# dnc.net
KiCad netlist of a schematic drawn in EAGLE
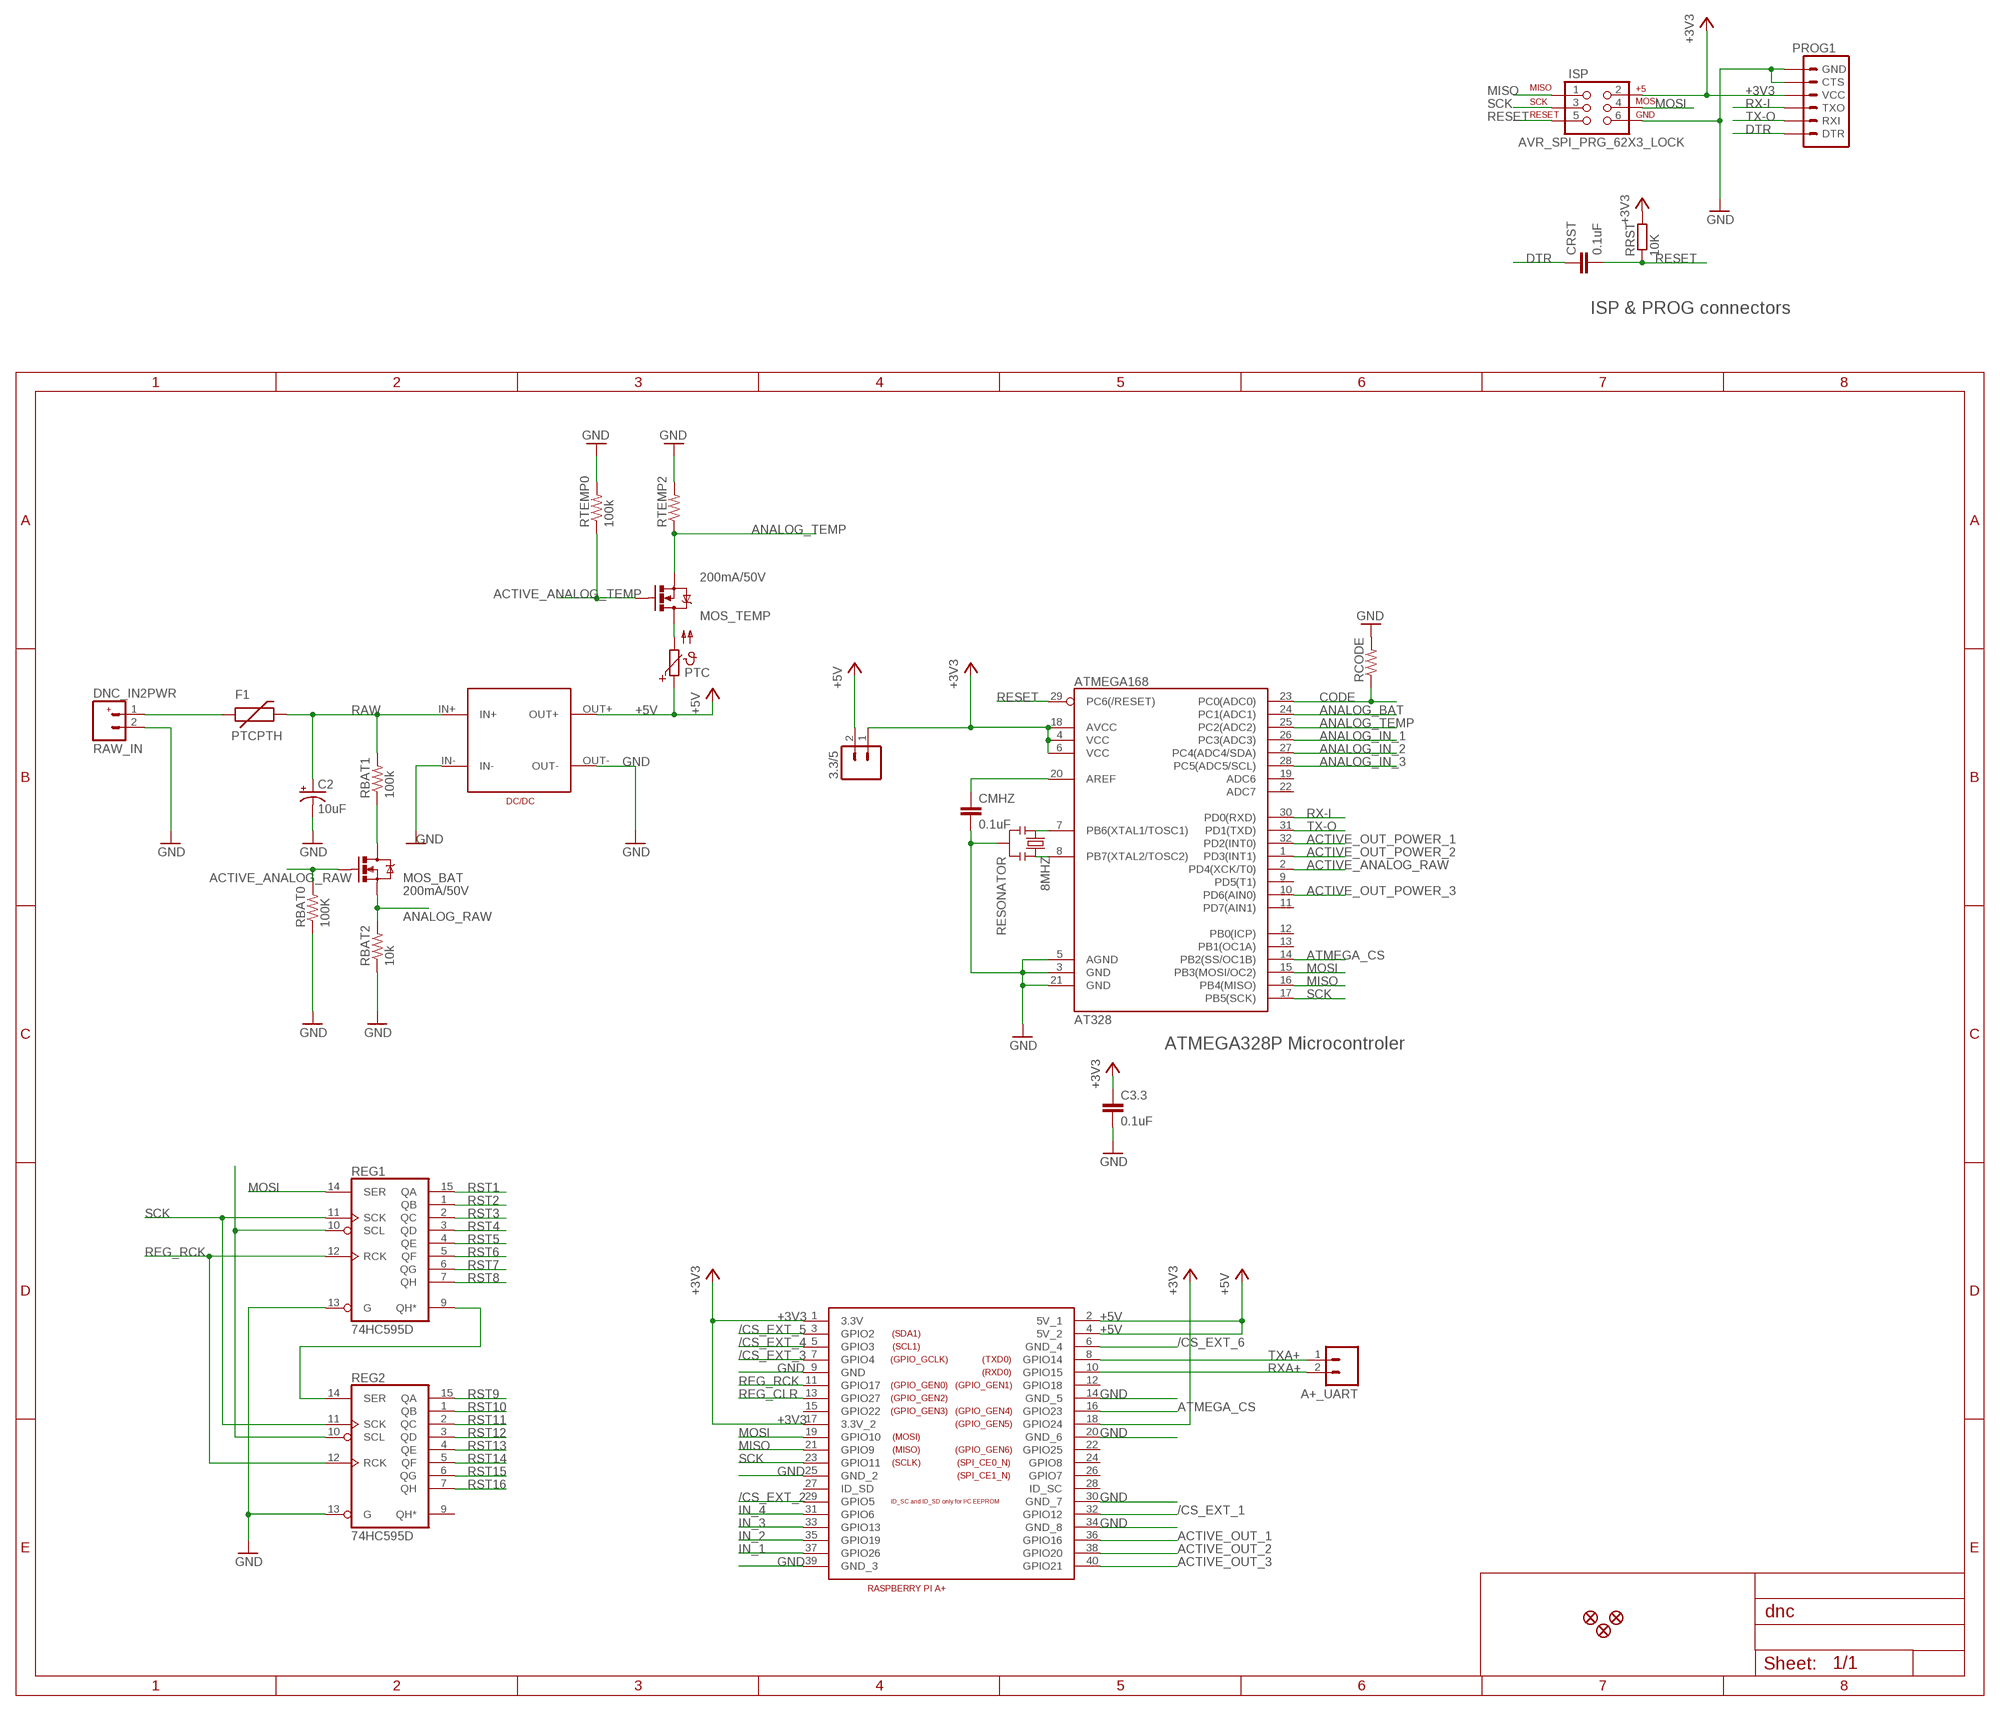
[diagram p0: schematic, sheet 1, part 1 of 2]
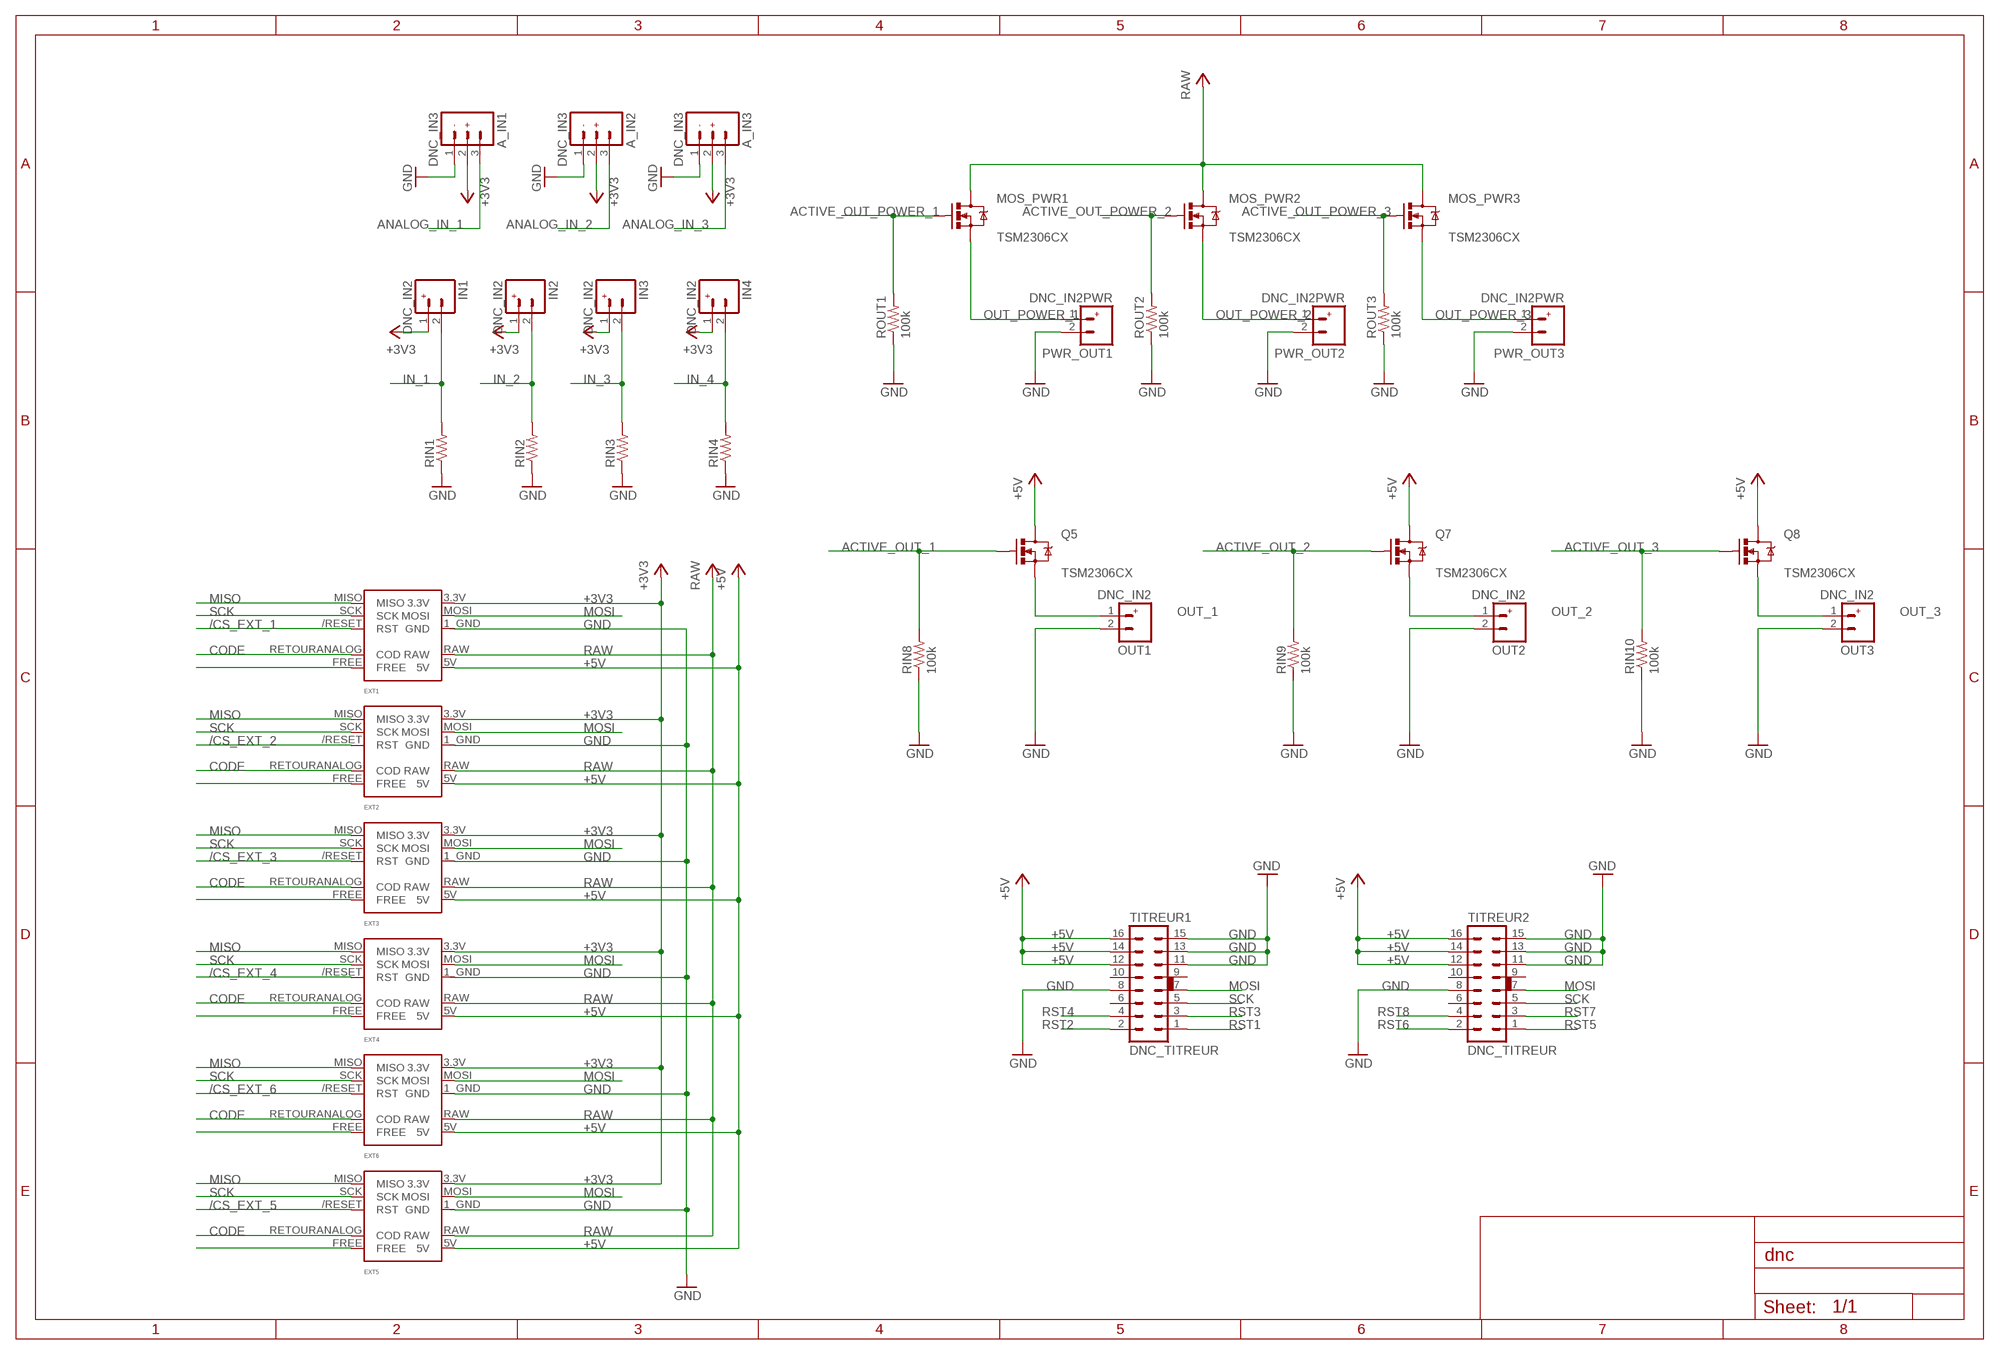
[diagram p1: schematic, sheet 1, part 2 of 2]

(export (version "E")
  (design (tool "Eeschema 10.0.6"))
  (components
    (comp (ref "3.3/5")
      (value "M02PTH3")
      (footprint "eagle-import:1X02_LONGPADS")
      (libsource (lib "eagle-import") (part "M02PTH3"))
    )
    (comp (ref "8MHZ")
      (value "RESONATOR")
      (footprint "eagle-import:RESONATOR_7MM")
      (libsource (lib "eagle-import") (part "RESONATOR"))
    )
    (comp (ref "A+_UART")
      (value "M02LOCK_LONGPADS")
      (footprint "eagle-import:1X02_LOCK_LONGPADS")
      (libsource (lib "eagle-import") (part "M02LOCK_LONGPADS"))
    )
    (comp (ref "AT328")
      (value "ATMEGA168")
      (footprint "eagle-import:TQFP32-08")
      (libsource (lib "eagle-import") (part "ATMEGA168"))
    )
    (comp (ref "A_IN1")
      (value "DNC_IN3")
      (footprint "eagle-import:DNC_IN3")
      (libsource (lib "eagle-import") (part "DNC_IN3"))
    )
    (comp (ref "A_IN2")
      (value "DNC_IN3")
      (footprint "eagle-import:DNC_IN3")
      (libsource (lib "eagle-import") (part "DNC_IN3"))
    )
    (comp (ref "A_IN3")
      (value "DNC_IN3")
      (footprint "eagle-import:DNC_IN3")
      (libsource (lib "eagle-import") (part "DNC_IN3"))
    )
    (comp (ref "C2")
      (value "10uF")
      (footprint "eagle-import:EIA3216")
      (libsource (lib "eagle-import") (part "CAP_POL1206"))
    )
    (comp (ref "C3.3")
      (value "0.1uF")
      (footprint "eagle-import:C0805")
      (libsource (lib "eagle-import") (part "C-EUC0805"))
    )
    (comp (ref "CMHZ")
      (value "0.1uF")
      (footprint "eagle-import:C0805")
      (libsource (lib "eagle-import") (part "C-EUC0805"))
    )
    (comp (ref "CRST")
      (value "0.1uF")
      (footprint "eagle-import:C0805")
      (libsource (lib "eagle-import") (part "C-EUC0805"))
    )
    (comp (ref "EXT1")
      (value "EXT-DNC")
      (footprint "eagle-import:EXTPINDNC")
      (libsource (lib "eagle-import") (part "EXT-DNC"))
    )
    (comp (ref "EXT2")
      (value "EXT-DNC")
      (footprint "eagle-import:EXTPINDNC")
      (libsource (lib "eagle-import") (part "EXT-DNC"))
    )
    (comp (ref "EXT3")
      (value "EXT-DNC")
      (footprint "eagle-import:EXTPINDNC")
      (libsource (lib "eagle-import") (part "EXT-DNC"))
    )
    (comp (ref "EXT4")
      (value "EXT-DNC")
      (footprint "eagle-import:EXTPINDNC")
      (libsource (lib "eagle-import") (part "EXT-DNC"))
    )
    (comp (ref "EXT5")
      (value "EXT-DNC")
      (footprint "eagle-import:EXTPINDNC")
      (libsource (lib "eagle-import") (part "EXT-DNC"))
    )
    (comp (ref "EXT6")
      (value "EXT-DNC")
      (footprint "eagle-import:EXTPINDNC")
      (libsource (lib "eagle-import") (part "EXT-DNC"))
    )
    (comp (ref "F1")
      (value "PTCPTH")
      (footprint "eagle-import:PTC")
      (libsource (lib "eagle-import") (part "PTCPTH"))
    )
    (comp (ref "IN1")
      (value "DNC_IN2")
      (footprint "eagle-import:DNC_IN2")
      (libsource (lib "eagle-import") (part "DNC_IN2"))
    )
    (comp (ref "IN2")
      (value "DNC_IN2")
      (footprint "eagle-import:DNC_IN2")
      (libsource (lib "eagle-import") (part "DNC_IN2"))
    )
    (comp (ref "IN3")
      (value "DNC_IN2")
      (footprint "eagle-import:DNC_IN2")
      (libsource (lib "eagle-import") (part "DNC_IN2"))
    )
    (comp (ref "IN4")
      (value "DNC_IN2")
      (footprint "eagle-import:DNC_IN2")
      (libsource (lib "eagle-import") (part "DNC_IN2"))
    )
    (comp (ref "ISP")
      (value "AVR_SPI_PRG_62X3_LOCK")
      (footprint "eagle-import:2X3_LOCK")
      (libsource (lib "eagle-import") (part "AVR_SPI_PRG_62X3_LOCK"))
    )
    (comp (ref "JP13")
      (value "FIDUCIAL1X2.5")
      (footprint "eagle-import:FIDUCIAL-1X2.5")
      (libsource (lib "eagle-import") (part "FIDUCIAL1X2.5"))
    )
    (comp (ref "JP14")
      (value "FIDUCIAL1X2.5")
      (footprint "eagle-import:FIDUCIAL-1X2.5")
      (libsource (lib "eagle-import") (part "FIDUCIAL1X2.5"))
    )
    (comp (ref "JP19")
      (value "FIDUCIAL1X2.5")
      (footprint "eagle-import:FIDUCIAL-1X2.5")
      (libsource (lib "eagle-import") (part "FIDUCIAL1X2.5"))
    )
    (comp (ref "MOS_BAT")
      (value "200mA/50V")
      (footprint "eagle-import:SOT23-3")
      (libsource (lib "eagle-import") (part "MOSFET-NCHANNELBSS138"))
    )
    (comp (ref "MOS_PWR1")
      (value "TSM2306CX")
      (footprint "eagle-import:SOT323")
      (libsource (lib "eagle-import") (part "MOSFET-NCHANNEL2N7002PW"))
    )
    (comp (ref "MOS_PWR2")
      (value "TSM2306CX")
      (footprint "eagle-import:SOT323")
      (libsource (lib "eagle-import") (part "MOSFET-NCHANNEL2N7002PW"))
    )
    (comp (ref "MOS_PWR3")
      (value "TSM2306CX")
      (footprint "eagle-import:SOT323")
      (libsource (lib "eagle-import") (part "MOSFET-NCHANNEL2N7002PW"))
    )
    (comp (ref "MOS_TEMP")
      (value "200mA/50V")
      (footprint "eagle-import:SOT23-3")
      (libsource (lib "eagle-import") (part "MOSFET-NCHANNELBSS138"))
    )
    (comp (ref "OUT1")
      (value "DNC_IN2")
      (footprint "eagle-import:DNC_IN2")
      (libsource (lib "eagle-import") (part "DNC_IN2"))
    )
    (comp (ref "OUT2")
      (value "DNC_IN2")
      (footprint "eagle-import:DNC_IN2")
      (libsource (lib "eagle-import") (part "DNC_IN2"))
    )
    (comp (ref "OUT3")
      (value "DNC_IN2")
      (footprint "eagle-import:DNC_IN2")
      (libsource (lib "eagle-import") (part "DNC_IN2"))
    )
    (comp (ref "PROG1")
      (value "ARDUINO_SERIAL_PROGRAMLOCK")
      (footprint "eagle-import:1X06_LOCK")
      (libsource (lib "eagle-import") (part "ARDUINO_SERIAL_PROGRAMLOCK"))
    )
    (comp (ref "PTC")
      (value "PTC679")
      (footprint "eagle-import:P679")
      (libsource (lib "eagle-import") (part "PTC679"))
    )
    (comp (ref "PWR_OUT1")
      (value "DNC_IN2PWR")
      (footprint "eagle-import:DNC_IN2_PWR")
      (libsource (lib "eagle-import") (part "DNC_IN2PWR"))
    )
    (comp (ref "PWR_OUT2")
      (value "DNC_IN2PWR")
      (footprint "eagle-import:DNC_IN2_PWR")
      (libsource (lib "eagle-import") (part "DNC_IN2PWR"))
    )
    (comp (ref "PWR_OUT3")
      (value "DNC_IN2PWR")
      (footprint "eagle-import:DNC_IN2_PWR")
      (libsource (lib "eagle-import") (part "DNC_IN2PWR"))
    )
    (comp (ref "Q5")
      (value "TSM2306CX")
      (footprint "eagle-import:SOT323")
      (libsource (lib "eagle-import") (part "MOSFET-NCHANNEL2N7002PW"))
    )
    (comp (ref "Q7")
      (value "TSM2306CX")
      (footprint "eagle-import:SOT323")
      (libsource (lib "eagle-import") (part "MOSFET-NCHANNEL2N7002PW"))
    )
    (comp (ref "Q8")
      (value "TSM2306CX")
      (footprint "eagle-import:SOT323")
      (libsource (lib "eagle-import") (part "MOSFET-NCHANNEL2N7002PW"))
    )
    (comp (ref "RAW_IN")
      (value "DNC_IN2PWR")
      (footprint "eagle-import:DNC_IN2_PWR")
      (libsource (lib "eagle-import") (part "DNC_IN2PWR"))
    )
    (comp (ref "RBAT0")
      (value "100K")
      (footprint "eagle-import:0603-RES")
      (libsource (lib "eagle-import") (part "RESISTOR0603-RES"))
    )
    (comp (ref "RBAT1")
      (value "100k")
      (footprint "eagle-import:0603-RES")
      (libsource (lib "eagle-import") (part "RESISTOR0603-RES"))
    )
    (comp (ref "RBAT2")
      (value "10k")
      (footprint "eagle-import:0603-RES")
      (libsource (lib "eagle-import") (part "RESISTOR0603-RES"))
    )
    (comp (ref "RCODE")
      (value "RESISTOR0603-RES")
      (footprint "eagle-import:0603-RES")
      (libsource (lib "eagle-import") (part "RESISTOR0603-RES"))
    )
    (comp (ref "REG1")
      (value "74HC595D")
      (footprint "eagle-import:SO16")
      (libsource (lib "eagle-import") (part "74595DHC"))
    )
    (comp (ref "REG2")
      (value "74HC595D")
      (footprint "eagle-import:SO16")
      (libsource (lib "eagle-import") (part "74595DHC"))
    )
    (comp (ref "RIN1")
      (value "RESISTOR0603-RES")
      (footprint "eagle-import:0603-RES")
      (libsource (lib "eagle-import") (part "RESISTOR0603-RES"))
    )
    (comp (ref "RIN2")
      (value "RESISTOR0603-RES")
      (footprint "eagle-import:0603-RES")
      (libsource (lib "eagle-import") (part "RESISTOR0603-RES"))
    )
    (comp (ref "RIN3")
      (value "RESISTOR0603-RES")
      (footprint "eagle-import:0603-RES")
      (libsource (lib "eagle-import") (part "RESISTOR0603-RES"))
    )
    (comp (ref "RIN4")
      (value "RESISTOR0603-RES")
      (footprint "eagle-import:0603-RES")
      (libsource (lib "eagle-import") (part "RESISTOR0603-RES"))
    )
    (comp (ref "RIN8")
      (value "100k")
      (footprint "eagle-import:0603-RES")
      (libsource (lib "eagle-import") (part "RESISTOR0603-RES"))
    )
    (comp (ref "RIN9")
      (value "100k")
      (footprint "eagle-import:0603-RES")
      (libsource (lib "eagle-import") (part "RESISTOR0603-RES"))
    )
    (comp (ref "RIN10")
      (value "100k")
      (footprint "eagle-import:0603-RES")
      (libsource (lib "eagle-import") (part "RESISTOR0603-RES"))
    )
    (comp (ref "ROUT1")
      (value "100k")
      (footprint "eagle-import:0603-RES")
      (libsource (lib "eagle-import") (part "RESISTOR0603-RES"))
    )
    (comp (ref "ROUT2")
      (value "100k")
      (footprint "eagle-import:0603-RES")
      (libsource (lib "eagle-import") (part "RESISTOR0603-RES"))
    )
    (comp (ref "ROUT3")
      (value "100k")
      (footprint "eagle-import:0603-RES")
      (libsource (lib "eagle-import") (part "RESISTOR0603-RES"))
    )
    (comp (ref "RRST")
      (value "10K")
      (footprint "eagle-import:R0603")
      (libsource (lib "eagle-import") (part "R-EU_R0603"))
    )
    (comp (ref "RTEMP0")
      (value "100k")
      (footprint "eagle-import:0603-RES")
      (libsource (lib "eagle-import") (part "RESISTOR0603-RES"))
    )
    (comp (ref "RTEMP2")
      (value "RESISTOR0603-RES")
      (footprint "eagle-import:0603-RES")
      (libsource (lib "eagle-import") (part "RESISTOR0603-RES"))
    )
    (comp (ref "TITREUR1")
      (value "DNC_TITREUR")
      (footprint "eagle-import:DNC_TITREUR")
      (libsource (lib "eagle-import") (part "DNC_TITREUR"))
    )
    (comp (ref "TITREUR2")
      (value "DNC_TITREUR")
      (footprint "eagle-import:DNC_TITREUR")
      (libsource (lib "eagle-import") (part "DNC_TITREUR"))
    )
    (comp (ref "U$4")
      (value "RASPIA+")
      (footprint "eagle-import:RASPIA+")
      (libsource (lib "eagle-import") (part "RASPIA+"))
    )
    (comp (ref "U$5")
      (value "DC/DC_SEED")
      (footprint "eagle-import:DC_DC_SEED")
      (libsource (lib "eagle-import") (part "DC/DC_SEED"))
    )
  )
  (nets
    (net (code "1") (name "+3V3") (class "Default")
      (node (ref "3.3/5") (pin "1") (pinfunction "1_1") (pintype "passive"))
      (node (ref "AT328") (pin "18") (pinfunction "AVCC_18") (pintype "bidirectional"))
      (node (ref "AT328") (pin "4") (pinfunction "VCC_4") (pintype "bidirectional"))
      (node (ref "AT328") (pin "6") (pinfunction "VCC_6") (pintype "bidirectional"))
      (node (ref "A_IN1") (pin "2") (pinfunction "2_2") (pintype "passive"))
      (node (ref "A_IN2") (pin "2") (pinfunction "2_2") (pintype "passive"))
      (node (ref "A_IN3") (pin "2") (pinfunction "2_2") (pintype "passive"))
      (node (ref "C3.3") (pin "1") (pinfunction "1_1") (pintype "passive"))
      (node (ref "EXT1") (pin "3.3V") (pinfunction "3.3V_3.3V") (pintype "bidirectional"))
      (node (ref "EXT2") (pin "3.3V") (pinfunction "3.3V_3.3V") (pintype "bidirectional"))
      (node (ref "EXT3") (pin "3.3V") (pinfunction "3.3V_3.3V") (pintype "bidirectional"))
      (node (ref "EXT4") (pin "3.3V") (pinfunction "3.3V_3.3V") (pintype "bidirectional"))
      (node (ref "EXT5") (pin "3.3V") (pinfunction "3.3V_3.3V") (pintype "bidirectional"))
      (node (ref "EXT6") (pin "3.3V") (pinfunction "3.3V_3.3V") (pintype "bidirectional"))
      (node (ref "IN1") (pin "1") (pinfunction "1_1") (pintype "passive"))
      (node (ref "IN2") (pin "1") (pinfunction "1_1") (pintype "passive"))
      (node (ref "IN3") (pin "1") (pinfunction "1_1") (pintype "passive"))
      (node (ref "IN4") (pin "1") (pinfunction "1_1") (pintype "passive"))
      (node (ref "ISP") (pin "2") (pinfunction "2_2") (pintype "passive"))
      (node (ref "PROG1") (pin "4") (pinfunction "VCC_4") (pintype "passive"))
      (node (ref "RRST") (pin "2") (pinfunction "2_2") (pintype "passive"))
      (node (ref "U$4") (pin "1") (pinfunction "3.3V_1") (pintype "bidirectional"))
      (node (ref "U$4") (pin "17") (pinfunction "3.3V_2_17") (pintype "bidirectional"))
      (node (ref "U$4") (pin "18") (pinfunction "GPIO24_18") (pintype "bidirectional"))
    )
    (net (code "2") (name "+5V") (class "Default")
      (node (ref "3.3/5") (pin "2") (pinfunction "2_2") (pintype "passive"))
      (node (ref "EXT1") (pin "5V") (pinfunction "5V_5V") (pintype "bidirectional"))
      (node (ref "EXT2") (pin "5V") (pinfunction "5V_5V") (pintype "bidirectional"))
      (node (ref "EXT3") (pin "5V") (pinfunction "5V_5V") (pintype "bidirectional"))
      (node (ref "EXT4") (pin "5V") (pinfunction "5V_5V") (pintype "bidirectional"))
      (node (ref "EXT5") (pin "5V") (pinfunction "5V_5V") (pintype "bidirectional"))
      (node (ref "EXT6") (pin "5V") (pinfunction "5V_5V") (pintype "bidirectional"))
      (node (ref "PTC") (pin "1") (pinfunction "1_1") (pintype "passive"))
      (node (ref "Q5") (pin "3") (pinfunction "D_3") (pintype "passive"))
      (node (ref "Q7") (pin "3") (pinfunction "D_3") (pintype "passive"))
      (node (ref "Q8") (pin "3") (pinfunction "D_3") (pintype "passive"))
      (node (ref "TITREUR1") (pin "12") (pinfunction "12_12") (pintype "passive"))
      (node (ref "TITREUR1") (pin "14") (pinfunction "14_14") (pintype "passive"))
      (node (ref "TITREUR1") (pin "16") (pinfunction "16_16") (pintype "passive"))
      (node (ref "TITREUR2") (pin "12") (pinfunction "12_12") (pintype "passive"))
      (node (ref "TITREUR2") (pin "14") (pinfunction "14_14") (pintype "passive"))
      (node (ref "TITREUR2") (pin "16") (pinfunction "16_16") (pintype "passive"))
      (node (ref "U$4") (pin "2") (pinfunction "5V_1_2") (pintype "bidirectional"))
      (node (ref "U$4") (pin "4") (pinfunction "5V_2_4") (pintype "bidirectional"))
      (node (ref "U$5") (pin "OUT+") (pinfunction "OUT+_OUT+") (pintype "bidirectional"))
    )
    (net (code "3") (name "/ACTIVE_ANALOG_RAW") (class "Default")
      (node (ref "AT328") (pin "2") (pinfunction "PD4(XCK/T0)_2") (pintype "bidirectional"))
      (node (ref "MOS_BAT") (pin "1") (pinfunction "G_1") (pintype "passive"))
      (node (ref "RBAT0") (pin "2") (pinfunction "2_2") (pintype "passive"))
    )
    (net (code "4") (name "/ACTIVE_ANALOG_TEMP") (class "Default")
      (node (ref "MOS_TEMP") (pin "1") (pinfunction "G_1") (pintype "passive"))
      (node (ref "RTEMP0") (pin "1") (pinfunction "1_1") (pintype "passive"))
    )
    (net (code "5") (name "/ACTIVE_OUT_1") (class "Default")
      (node (ref "Q5") (pin "1") (pinfunction "G_1") (pintype "passive"))
      (node (ref "RIN8") (pin "2") (pinfunction "2_2") (pintype "passive"))
      (node (ref "U$4") (pin "36") (pinfunction "GPIO16_36") (pintype "bidirectional"))
    )
    (net (code "6") (name "/ACTIVE_OUT_2") (class "Default")
      (node (ref "Q7") (pin "1") (pinfunction "G_1") (pintype "passive"))
      (node (ref "RIN9") (pin "2") (pinfunction "2_2") (pintype "passive"))
      (node (ref "U$4") (pin "38") (pinfunction "GPIO20_38") (pintype "bidirectional"))
    )
    (net (code "7") (name "/ACTIVE_OUT_3") (class "Default")
      (node (ref "Q8") (pin "1") (pinfunction "G_1") (pintype "passive"))
      (node (ref "RIN10") (pin "2") (pinfunction "2_2") (pintype "passive"))
      (node (ref "U$4") (pin "40") (pinfunction "GPIO21_40") (pintype "bidirectional"))
    )
    (net (code "8") (name "/ACTIVE_OUT_POWER_1") (class "Default")
      (node (ref "AT328") (pin "32") (pinfunction "PD2(INT0)_32") (pintype "bidirectional"))
      (node (ref "MOS_PWR1") (pin "1") (pinfunction "G_1") (pintype "passive"))
      (node (ref "ROUT1") (pin "2") (pinfunction "2_2") (pintype "passive"))
    )
    (net (code "9") (name "/ACTIVE_OUT_POWER_2") (class "Default")
      (node (ref "AT328") (pin "1") (pinfunction "PD3(INT1)_1") (pintype "bidirectional"))
      (node (ref "MOS_PWR2") (pin "1") (pinfunction "G_1") (pintype "passive"))
      (node (ref "ROUT2") (pin "2") (pinfunction "2_2") (pintype "passive"))
    )
    (net (code "10") (name "/ACTIVE_OUT_POWER_3") (class "Default")
      (node (ref "AT328") (pin "10") (pinfunction "PD6(AIN0)_10") (pintype "bidirectional"))
      (node (ref "MOS_PWR3") (pin "1") (pinfunction "G_1") (pintype "passive"))
      (node (ref "ROUT3") (pin "2") (pinfunction "2_2") (pintype "passive"))
    )
    (net (code "11") (name "/ANALOG_BAT") (class "Default")
      (node (ref "AT328") (pin "24") (pinfunction "PC1(ADC1)_24") (pintype "bidirectional"))
    )
    (net (code "12") (name "/ANALOG_IN_1") (class "Default")
      (node (ref "AT328") (pin "26") (pinfunction "PC3(ADC3)_26") (pintype "bidirectional"))
      (node (ref "A_IN1") (pin "3") (pinfunction "3_3") (pintype "passive"))
    )
    (net (code "13") (name "/ANALOG_IN_2") (class "Default")
      (node (ref "AT328") (pin "27") (pinfunction "PC4(ADC4/SDA)_27") (pintype "bidirectional"))
      (node (ref "A_IN2") (pin "3") (pinfunction "3_3") (pintype "passive"))
    )
    (net (code "14") (name "/ANALOG_IN_3") (class "Default")
      (node (ref "AT328") (pin "28") (pinfunction "PC5(ADC5/SCL)_28") (pintype "bidirectional"))
      (node (ref "A_IN3") (pin "3") (pinfunction "3_3") (pintype "passive"))
    )
    (net (code "15") (name "/ANALOG_RAW") (class "Default")
      (node (ref "MOS_BAT") (pin "2") (pinfunction "S_2") (pintype "passive"))
      (node (ref "RBAT2") (pin "2") (pinfunction "2_2") (pintype "passive"))
    )
    (net (code "16") (name "/ANALOG_TEMP") (class "Default")
      (node (ref "AT328") (pin "25") (pinfunction "PC2(ADC2)_25") (pintype "bidirectional"))
      (node (ref "MOS_TEMP") (pin "2") (pinfunction "S_2") (pintype "passive"))
      (node (ref "RTEMP2") (pin "1") (pinfunction "1_1") (pintype "passive"))
    )
    (net (code "17") (name "/ATMEGA_CS") (class "Default")
      (node (ref "AT328") (pin "14") (pinfunction "PB2(SS/OC1B)_14") (pintype "bidirectional"))
      (node (ref "U$4") (pin "16") (pinfunction "GPIO23_16") (pintype "bidirectional"))
    )
    (net (code "18") (name "/CODE") (class "Default")
      (node (ref "AT328") (pin "23") (pinfunction "PC0(ADC0)_23") (pintype "bidirectional"))
      (node (ref "EXT1") (pin "RETOURANALOG") (pinfunction "COD_RETOURANALOG") (pintype "bidirectional"))
      (node (ref "EXT2") (pin "RETOURANALOG") (pinfunction "COD_RETOURANALOG") (pintype "bidirectional"))
      (node (ref "EXT3") (pin "RETOURANALOG") (pinfunction "COD_RETOURANALOG") (pintype "bidirectional"))
      (node (ref "EXT4") (pin "RETOURANALOG") (pinfunction "COD_RETOURANALOG") (pintype "bidirectional"))
      (node (ref "EXT5") (pin "RETOURANALOG") (pinfunction "COD_RETOURANALOG") (pintype "bidirectional"))
      (node (ref "EXT6") (pin "RETOURANALOG") (pinfunction "COD_RETOURANALOG") (pintype "bidirectional"))
      (node (ref "RCODE") (pin "1") (pinfunction "1_1") (pintype "passive"))
    )
    (net (code "19") (name "/DTR") (class "Default")
      (node (ref "CRST") (pin "1") (pinfunction "1_1") (pintype "passive"))
      (node (ref "PROG1") (pin "1") (pinfunction "DTR_1") (pintype "passive"))
    )
    (net (code "20") (name "/IN_1") (class "Default")
      (node (ref "IN1") (pin "2") (pinfunction "2_2") (pintype "passive"))
      (node (ref "RIN1") (pin "2") (pinfunction "2_2") (pintype "passive"))
      (node (ref "U$4") (pin "37") (pinfunction "GPIO26_37") (pintype "bidirectional"))
    )
    (net (code "21") (name "/IN_2") (class "Default")
      (node (ref "IN2") (pin "2") (pinfunction "2_2") (pintype "passive"))
      (node (ref "RIN2") (pin "2") (pinfunction "2_2") (pintype "passive"))
      (node (ref "U$4") (pin "35") (pinfunction "GPIO19_35") (pintype "bidirectional"))
    )
    (net (code "22") (name "/IN_3") (class "Default")
      (node (ref "IN3") (pin "2") (pinfunction "2_2") (pintype "passive"))
      (node (ref "RIN3") (pin "2") (pinfunction "2_2") (pintype "passive"))
      (node (ref "U$4") (pin "33") (pinfunction "GPIO13_33") (pintype "bidirectional"))
    )
    (net (code "23") (name "/IN_4") (class "Default")
      (node (ref "IN4") (pin "2") (pinfunction "2_2") (pintype "passive"))
      (node (ref "RIN4") (pin "2") (pinfunction "2_2") (pintype "passive"))
      (node (ref "U$4") (pin "31") (pinfunction "GPIO6_31") (pintype "bidirectional"))
    )
    (net (code "24") (name "/MISO") (class "Default")
      (node (ref "AT328") (pin "16") (pinfunction "PB4(MISO)_16") (pintype "bidirectional"))
      (node (ref "EXT1") (pin "MISO") (pinfunction "MISO_MISO") (pintype "bidirectional"))
      (node (ref "EXT2") (pin "MISO") (pinfunction "MISO_MISO") (pintype "bidirectional"))
      (node (ref "EXT3") (pin "MISO") (pinfunction "MISO_MISO") (pintype "bidirectional"))
      (node (ref "EXT4") (pin "MISO") (pinfunction "MISO_MISO") (pintype "bidirectional"))
      (node (ref "EXT5") (pin "MISO") (pinfunction "MISO_MISO") (pintype "bidirectional"))
      (node (ref "EXT6") (pin "MISO") (pinfunction "MISO_MISO") (pintype "bidirectional"))
      (node (ref "ISP") (pin "1") (pinfunction "1_1") (pintype "passive"))
      (node (ref "U$4") (pin "21") (pinfunction "GPIO9_21") (pintype "bidirectional"))
    )
    (net (code "25") (name "/MOSI") (class "Default")
      (node (ref "AT328") (pin "15") (pinfunction "PB3(MOSI/OC2)_15") (pintype "bidirectional"))
      (node (ref "EXT1") (pin "MOSI") (pinfunction "MOSI_MOSI") (pintype "bidirectional"))
      (node (ref "EXT2") (pin "MOSI") (pinfunction "MOSI_MOSI") (pintype "bidirectional"))
      (node (ref "EXT3") (pin "MOSI") (pinfunction "MOSI_MOSI") (pintype "bidirectional"))
      (node (ref "EXT4") (pin "MOSI") (pinfunction "MOSI_MOSI") (pintype "bidirectional"))
      (node (ref "EXT5") (pin "MOSI") (pinfunction "MOSI_MOSI") (pintype "bidirectional"))
      (node (ref "EXT6") (pin "MOSI") (pinfunction "MOSI_MOSI") (pintype "bidirectional"))
      (node (ref "ISP") (pin "4") (pinfunction "4_4") (pintype "passive"))
      (node (ref "REG1") (pin "14") (pinfunction "SER_14") (pintype "input"))
      (node (ref "TITREUR1") (pin "7") (pinfunction "7_7") (pintype "passive"))
      (node (ref "TITREUR2") (pin "7") (pinfunction "7_7") (pintype "passive"))
      (node (ref "U$4") (pin "19") (pinfunction "GPIO10_19") (pintype "bidirectional"))
    )
    (net (code "26") (name "/OUT_1") (class "Default")
      (node (ref "OUT1") (pin "1") (pinfunction "1_1") (pintype "passive"))
      (node (ref "Q5") (pin "2") (pinfunction "S_2") (pintype "passive"))
    )
    (net (code "27") (name "/OUT_2") (class "Default")
      (node (ref "OUT2") (pin "1") (pinfunction "1_1") (pintype "passive"))
      (node (ref "Q7") (pin "2") (pinfunction "S_2") (pintype "passive"))
    )
    (net (code "28") (name "/OUT_3") (class "Default")
      (node (ref "OUT3") (pin "1") (pinfunction "1_1") (pintype "passive"))
      (node (ref "Q8") (pin "2") (pinfunction "S_2") (pintype "passive"))
    )
    (net (code "29") (name "/OUT_POWER_1") (class "Default")
      (node (ref "MOS_PWR1") (pin "2") (pinfunction "S_2") (pintype "passive"))
      (node (ref "PWR_OUT1") (pin "1") (pinfunction "1_1") (pintype "passive"))
    )
    (net (code "30") (name "/OUT_POWER_2") (class "Default")
      (node (ref "MOS_PWR2") (pin "2") (pinfunction "S_2") (pintype "passive"))
      (node (ref "PWR_OUT2") (pin "1") (pinfunction "1_1") (pintype "passive"))
    )
    (net (code "31") (name "/OUT_POWER_3") (class "Default")
      (node (ref "MOS_PWR3") (pin "2") (pinfunction "S_2") (pintype "passive"))
      (node (ref "PWR_OUT3") (pin "1") (pinfunction "1_1") (pintype "passive"))
    )
    (net (code "32") (name "/REG_CLR") (class "Default")
      (node (ref "REG1") (pin "10") (pinfunction "SCL_10") (pintype "input"))
      (node (ref "REG2") (pin "10") (pinfunction "SCL_10") (pintype "input"))
      (node (ref "U$4") (pin "13") (pinfunction "GPIO27_13") (pintype "bidirectional"))
    )
    (net (code "33") (name "/REG_RCK") (class "Default")
      (node (ref "REG1") (pin "12") (pinfunction "RCK_12") (pintype "input"))
      (node (ref "REG2") (pin "12") (pinfunction "RCK_12") (pintype "input"))
      (node (ref "U$4") (pin "11") (pinfunction "GPIO17_11") (pintype "bidirectional"))
    )
    (net (code "34") (name "/RESET") (class "Default")
      (node (ref "AT328") (pin "29") (pinfunction "PC6(/RESET)_29") (pintype "bidirectional"))
      (node (ref "CRST") (pin "2") (pinfunction "2_2") (pintype "passive"))
      (node (ref "ISP") (pin "5") (pinfunction "5_5") (pintype "passive"))
      (node (ref "RRST") (pin "1") (pinfunction "1_1") (pintype "passive"))
    )
    (net (code "35") (name "/RST1") (class "Default")
      (node (ref "REG1") (pin "15") (pinfunction "QA_15") (pintype "tri_state"))
      (node (ref "TITREUR1") (pin "1") (pinfunction "1_1") (pintype "passive"))
    )
    (net (code "36") (name "/RST2") (class "Default")
      (node (ref "REG1") (pin "1") (pinfunction "QB_1") (pintype "tri_state"))
      (node (ref "TITREUR1") (pin "2") (pinfunction "2_2") (pintype "passive"))
    )
    (net (code "37") (name "/RST3") (class "Default")
      (node (ref "REG1") (pin "2") (pinfunction "QC_2") (pintype "tri_state"))
      (node (ref "TITREUR1") (pin "3") (pinfunction "3_3") (pintype "passive"))
    )
    (net (code "38") (name "/RST4") (class "Default")
      (node (ref "REG1") (pin "3") (pinfunction "QD_3") (pintype "tri_state"))
      (node (ref "TITREUR1") (pin "4") (pinfunction "4_4") (pintype "passive"))
    )
    (net (code "39") (name "/RST5") (class "Default")
      (node (ref "REG1") (pin "4") (pinfunction "QE_4") (pintype "tri_state"))
      (node (ref "TITREUR2") (pin "1") (pinfunction "1_1") (pintype "passive"))
    )
    (net (code "40") (name "/RST6") (class "Default")
      (node (ref "REG1") (pin "5") (pinfunction "QF_5") (pintype "tri_state"))
      (node (ref "TITREUR2") (pin "2") (pinfunction "2_2") (pintype "passive"))
    )
    (net (code "41") (name "/RST7") (class "Default")
      (node (ref "REG1") (pin "6") (pinfunction "QG_6") (pintype "tri_state"))
      (node (ref "TITREUR2") (pin "3") (pinfunction "3_3") (pintype "passive"))
    )
    (net (code "42") (name "/RST8") (class "Default")
      (node (ref "REG1") (pin "7") (pinfunction "QH_7") (pintype "tri_state"))
      (node (ref "TITREUR2") (pin "4") (pinfunction "4_4") (pintype "passive"))
    )
    (net (code "43") (name "/RST9") (class "Default")
      (node (ref "REG2") (pin "15") (pinfunction "QA_15") (pintype "tri_state"))
    )
    (net (code "44") (name "/RST10") (class "Default")
      (node (ref "REG2") (pin "1") (pinfunction "QB_1") (pintype "tri_state"))
    )
    (net (code "45") (name "/RST11") (class "Default")
      (node (ref "REG2") (pin "2") (pinfunction "QC_2") (pintype "tri_state"))
    )
    (net (code "46") (name "/RST12") (class "Default")
      (node (ref "REG2") (pin "3") (pinfunction "QD_3") (pintype "tri_state"))
    )
    (net (code "47") (name "/RST13") (class "Default")
      (node (ref "REG2") (pin "4") (pinfunction "QE_4") (pintype "tri_state"))
    )
    (net (code "48") (name "/RST14") (class "Default")
      (node (ref "REG2") (pin "5") (pinfunction "QF_5") (pintype "tri_state"))
    )
    (net (code "49") (name "/RST15") (class "Default")
      (node (ref "REG2") (pin "6") (pinfunction "QG_6") (pintype "tri_state"))
    )
    (net (code "50") (name "/RST16") (class "Default")
      (node (ref "REG2") (pin "7") (pinfunction "QH_7") (pintype "tri_state"))
    )
    (net (code "51") (name "/RX-I") (class "Default")
      (node (ref "AT328") (pin "30") (pinfunction "PD0(RXD)_30") (pintype "bidirectional"))
      (node (ref "PROG1") (pin "3") (pinfunction "TXO_3") (pintype "passive"))
    )
    (net (code "52") (name "/RXA+") (class "Default")
      (node (ref "A+_UART") (pin "2") (pinfunction "2_2") (pintype "passive"))
      (node (ref "U$4") (pin "10") (pinfunction "GPIO15_10") (pintype "bidirectional"))
    )
    (net (code "53") (name "/SCK") (class "Default")
      (node (ref "AT328") (pin "17") (pinfunction "PB5(SCK)_17") (pintype "bidirectional"))
      (node (ref "EXT1") (pin "SCK") (pinfunction "SCK_SCK") (pintype "bidirectional"))
      (node (ref "EXT2") (pin "SCK") (pinfunction "SCK_SCK") (pintype "bidirectional"))
      (node (ref "EXT3") (pin "SCK") (pinfunction "SCK_SCK") (pintype "bidirectional"))
      (node (ref "EXT4") (pin "SCK") (pinfunction "SCK_SCK") (pintype "bidirectional"))
      (node (ref "EXT5") (pin "SCK") (pinfunction "SCK_SCK") (pintype "bidirectional"))
      (node (ref "EXT6") (pin "SCK") (pinfunction "SCK_SCK") (pintype "bidirectional"))
      (node (ref "ISP") (pin "3") (pinfunction "3_3") (pintype "passive"))
      (node (ref "REG1") (pin "11") (pinfunction "SCK_11") (pintype "input"))
      (node (ref "REG2") (pin "11") (pinfunction "SCK_11") (pintype "input"))
      (node (ref "TITREUR1") (pin "5") (pinfunction "5_5") (pintype "passive"))
      (node (ref "TITREUR2") (pin "5") (pinfunction "5_5") (pintype "passive"))
      (node (ref "U$4") (pin "23") (pinfunction "GPIO11_23") (pintype "bidirectional"))
    )
    (net (code "54") (name "/TX-O") (class "Default")
      (node (ref "AT328") (pin "31") (pinfunction "PD1(TXD)_31") (pintype "bidirectional"))
      (node (ref "PROG1") (pin "2") (pinfunction "RXI_2") (pintype "passive"))
    )
    (net (code "55") (name "/TXA+") (class "Default")
      (node (ref "A+_UART") (pin "1") (pinfunction "1_1") (pintype "passive"))
      (node (ref "U$4") (pin "8") (pinfunction "GPIO14_8") (pintype "bidirectional"))
    )
    (net (code "56") (name "/{slash}CS_EXT_1") (class "Default")
      (node (ref "EXT1") (pin "/RESET") (pinfunction "RST_/RESET") (pintype "bidirectional"))
      (node (ref "U$4") (pin "32") (pinfunction "GPIO12_32") (pintype "bidirectional"))
    )
    (net (code "57") (name "/{slash}CS_EXT_2") (class "Default")
      (node (ref "EXT2") (pin "/RESET") (pinfunction "RST_/RESET") (pintype "bidirectional"))
      (node (ref "U$4") (pin "29") (pinfunction "GPIO5_29") (pintype "bidirectional"))
    )
    (net (code "58") (name "/{slash}CS_EXT_3") (class "Default")
      (node (ref "EXT3") (pin "/RESET") (pinfunction "RST_/RESET") (pintype "bidirectional"))
      (node (ref "U$4") (pin "7") (pinfunction "GPIO4_7") (pintype "bidirectional"))
    )
    (net (code "59") (name "/{slash}CS_EXT_4") (class "Default")
      (node (ref "EXT4") (pin "/RESET") (pinfunction "RST_/RESET") (pintype "bidirectional"))
      (node (ref "U$4") (pin "5") (pinfunction "GPIO3_5") (pintype "bidirectional"))
    )
    (net (code "60") (name "/{slash}CS_EXT_5") (class "Default")
      (node (ref "EXT5") (pin "/RESET") (pinfunction "RST_/RESET") (pintype "bidirectional"))
      (node (ref "U$4") (pin "3") (pinfunction "GPIO2_3") (pintype "bidirectional"))
    )
    (net (code "61") (name "/{slash}CS_EXT_6") (class "Default")
      (node (ref "EXT6") (pin "/RESET") (pinfunction "RST_/RESET") (pintype "bidirectional"))
      (node (ref "U$4") (pin "6") (pinfunction "GND_4_6") (pintype "bidirectional"))
    )
    (net (code "62") (name "GND") (class "Default")
      (node (ref "8MHZ") (pin "2") (pinfunction "2_2") (pintype "passive"))
      (node (ref "AT328") (pin "21") (pinfunction "GND_21") (pintype "bidirectional"))
      (node (ref "AT328") (pin "3") (pinfunction "GND_3") (pintype "bidirectional"))
      (node (ref "AT328") (pin "5") (pinfunction "AGND_5") (pintype "bidirectional"))
      (node (ref "A_IN1") (pin "1") (pinfunction "1_1") (pintype "passive"))
      (node (ref "A_IN2") (pin "1") (pinfunction "1_1") (pintype "passive"))
      (node (ref "A_IN3") (pin "1") (pinfunction "1_1") (pintype "passive"))
      (node (ref "C2") (pin "C") (pinfunction "-_C") (pintype "passive"))
      (node (ref "C3.3") (pin "2") (pinfunction "2_2") (pintype "passive"))
      (node (ref "CMHZ") (pin "2") (pinfunction "2_2") (pintype "passive"))
      (node (ref "EXT1") (pin "1_GND") (pinfunction "GND_1_GND") (pintype "bidirectional"))
      (node (ref "EXT2") (pin "1_GND") (pinfunction "GND_1_GND") (pintype "bidirectional"))
      (node (ref "EXT3") (pin "1_GND") (pinfunction "GND_1_GND") (pintype "bidirectional"))
      (node (ref "EXT4") (pin "1_GND") (pinfunction "GND_1_GND") (pintype "bidirectional"))
      (node (ref "EXT5") (pin "1_GND") (pinfunction "GND_1_GND") (pintype "bidirectional"))
      (node (ref "EXT6") (pin "1_GND") (pinfunction "GND_1_GND") (pintype "bidirectional"))
      (node (ref "ISP") (pin "6") (pinfunction "6_6") (pintype "passive"))
      (node (ref "OUT1") (pin "2") (pinfunction "2_2") (pintype "passive"))
      (node (ref "OUT2") (pin "2") (pinfunction "2_2") (pintype "passive"))
      (node (ref "OUT3") (pin "2") (pinfunction "2_2") (pintype "passive"))
      (node (ref "PROG1") (pin "5") (pinfunction "CTS_5") (pintype "passive"))
      (node (ref "PROG1") (pin "6") (pinfunction "GND_6") (pintype "passive"))
      (node (ref "PWR_OUT1") (pin "2") (pinfunction "2_2") (pintype "passive"))
      (node (ref "PWR_OUT2") (pin "2") (pinfunction "2_2") (pintype "passive"))
      (node (ref "PWR_OUT3") (pin "2") (pinfunction "2_2") (pintype "passive"))
      (node (ref "RAW_IN") (pin "2") (pinfunction "2_2") (pintype "passive"))
      (node (ref "RBAT0") (pin "1") (pinfunction "1_1") (pintype "passive"))
      (node (ref "RBAT2") (pin "1") (pinfunction "1_1") (pintype "passive"))
      (node (ref "RCODE") (pin "2") (pinfunction "2_2") (pintype "passive"))
      (node (ref "REG1") (pin "13") (pinfunction "G_13") (pintype "input"))
      (node (ref "REG2") (pin "13") (pinfunction "G_13") (pintype "input"))
      (node (ref "RIN1") (pin "1") (pinfunction "1_1") (pintype "passive"))
      (node (ref "RIN10") (pin "1") (pinfunction "1_1") (pintype "passive"))
      (node (ref "RIN2") (pin "1") (pinfunction "1_1") (pintype "passive"))
      (node (ref "RIN3") (pin "1") (pinfunction "1_1") (pintype "passive"))
      (node (ref "RIN4") (pin "1") (pinfunction "1_1") (pintype "passive"))
      (node (ref "RIN8") (pin "1") (pinfunction "1_1") (pintype "passive"))
      (node (ref "RIN9") (pin "1") (pinfunction "1_1") (pintype "passive"))
      (node (ref "ROUT1") (pin "1") (pinfunction "1_1") (pintype "passive"))
      (node (ref "ROUT2") (pin "1") (pinfunction "1_1") (pintype "passive"))
      (node (ref "ROUT3") (pin "1") (pinfunction "1_1") (pintype "passive"))
      (node (ref "RTEMP0") (pin "2") (pinfunction "2_2") (pintype "passive"))
      (node (ref "RTEMP2") (pin "2") (pinfunction "2_2") (pintype "passive"))
      (node (ref "TITREUR1") (pin "11") (pinfunction "11_11") (pintype "passive"))
      (node (ref "TITREUR1") (pin "13") (pinfunction "13_13") (pintype "passive"))
      (node (ref "TITREUR1") (pin "15") (pinfunction "15_15") (pintype "passive"))
      (node (ref "TITREUR1") (pin "8") (pinfunction "8_8") (pintype "passive"))
      (node (ref "TITREUR2") (pin "11") (pinfunction "11_11") (pintype "passive"))
      (node (ref "TITREUR2") (pin "13") (pinfunction "13_13") (pintype "passive"))
      (node (ref "TITREUR2") (pin "15") (pinfunction "15_15") (pintype "passive"))
      (node (ref "TITREUR2") (pin "8") (pinfunction "8_8") (pintype "passive"))
      (node (ref "U$4") (pin "14") (pinfunction "GND_5_14") (pintype "bidirectional"))
      (node (ref "U$4") (pin "20") (pinfunction "GND_6_20") (pintype "bidirectional"))
      (node (ref "U$4") (pin "25") (pinfunction "GND_2_25") (pintype "bidirectional"))
      (node (ref "U$4") (pin "30") (pinfunction "GND_7_30") (pintype "bidirectional"))
      (node (ref "U$4") (pin "34") (pinfunction "GND_8_34") (pintype "bidirectional"))
      (node (ref "U$4") (pin "39") (pinfunction "GND_3_39") (pintype "bidirectional"))
      (node (ref "U$4") (pin "9") (pinfunction "GND_9") (pintype "bidirectional"))
      (node (ref "U$5") (pin "IN-") (pinfunction "IN-_IN-") (pintype "bidirectional"))
      (node (ref "U$5") (pin "OUT-") (pinfunction "OUT-_OUT-") (pintype "bidirectional"))
    )
    (net (code "63") (name "Net-(AT328-AREF)") (class "Default")
      (node (ref "AT328") (pin "20") (pinfunction "AREF_20") (pintype "bidirectional"))
      (node (ref "CMHZ") (pin "1") (pinfunction "1_1") (pintype "passive"))
    )
    (net (code "64") (name "Net-(AT328-PB6(XTAL1{slash}TOSC1))") (class "Default")
      (node (ref "8MHZ") (pin "1") (pinfunction "1_1") (pintype "passive"))
      (node (ref "AT328") (pin "7") (pinfunction "PB6(XTAL1/TOSC1)_7") (pintype "bidirectional"))
    )
    (net (code "65") (name "Net-(AT328-PB7(XTAL2{slash}TOSC2))") (class "Default")
      (node (ref "8MHZ") (pin "3") (pinfunction "3_3") (pintype "passive"))
      (node (ref "AT328") (pin "8") (pinfunction "PB7(XTAL2/TOSC2)_8") (pintype "bidirectional"))
    )
    (net (code "66") (name "Net-(F1-1)") (class "Default")
      (node (ref "F1") (pin "P$1") (pinfunction "1_P$1") (pintype "bidirectional"))
      (node (ref "RAW_IN") (pin "1") (pinfunction "1_1") (pintype "passive"))
    )
    (net (code "67") (name "Net-(MOS_BAT-D)") (class "Default")
      (node (ref "MOS_BAT") (pin "3") (pinfunction "D_3") (pintype "passive"))
      (node (ref "RBAT1") (pin "1") (pinfunction "1_1") (pintype "passive"))
    )
    (net (code "68") (name "Net-(MOS_TEMP-D)") (class "Default")
      (node (ref "MOS_TEMP") (pin "3") (pinfunction "D_3") (pintype "passive"))
      (node (ref "PTC") (pin "2") (pinfunction "2_2") (pintype "passive"))
    )
    (net (code "69") (name "Net-(REG1A-QH*)") (class "Default")
      (node (ref "REG1") (pin "9") (pinfunction "QH*_9") (pintype "tri_state"))
      (node (ref "REG2") (pin "14") (pinfunction "SER_14") (pintype "input"))
    )
    (net (code "70") (name "RAW") (class "Default")
      (node (ref "C2") (pin "A") (pinfunction "+_A") (pintype "passive"))
      (node (ref "EXT1") (pin "RAW") (pinfunction "RAW_RAW") (pintype "bidirectional"))
      (node (ref "EXT2") (pin "RAW") (pinfunction "RAW_RAW") (pintype "bidirectional"))
      (node (ref "EXT3") (pin "RAW") (pinfunction "RAW_RAW") (pintype "bidirectional"))
      (node (ref "EXT4") (pin "RAW") (pinfunction "RAW_RAW") (pintype "bidirectional"))
      (node (ref "EXT5") (pin "RAW") (pinfunction "RAW_RAW") (pintype "bidirectional"))
      (node (ref "EXT6") (pin "RAW") (pinfunction "RAW_RAW") (pintype "bidirectional"))
      (node (ref "F1") (pin "P$2") (pinfunction "2_P$2") (pintype "bidirectional"))
      (node (ref "MOS_PWR1") (pin "3") (pinfunction "D_3") (pintype "passive"))
      (node (ref "MOS_PWR2") (pin "3") (pinfunction "D_3") (pintype "passive"))
      (node (ref "MOS_PWR3") (pin "3") (pinfunction "D_3") (pintype "passive"))
      (node (ref "RBAT1") (pin "2") (pinfunction "2_2") (pintype "passive"))
      (node (ref "U$5") (pin "IN+") (pinfunction "IN+_IN+") (pintype "bidirectional"))
    )
    (net (code "71") (name "unconnected-(AT328-ADC6-Pad19)") (class "Default")
      (node (ref "AT328") (pin "19") (pinfunction "ADC6_19") (pintype "bidirectional"))
    )
    (net (code "72") (name "unconnected-(AT328-ADC7-Pad22)") (class "Default")
      (node (ref "AT328") (pin "22") (pinfunction "ADC7_22") (pintype "bidirectional"))
    )
    (net (code "73") (name "unconnected-(AT328-PB0(ICP)-Pad12)") (class "Default")
      (node (ref "AT328") (pin "12") (pinfunction "PB0(ICP)_12") (pintype "bidirectional"))
    )
    (net (code "74") (name "unconnected-(AT328-PB1(OC1A)-Pad13)") (class "Default")
      (node (ref "AT328") (pin "13") (pinfunction "PB1(OC1A)_13") (pintype "bidirectional"))
    )
    (net (code "75") (name "unconnected-(AT328-PD5(T1)-Pad9)") (class "Default")
      (node (ref "AT328") (pin "9") (pinfunction "PD5(T1)_9") (pintype "bidirectional"))
    )
    (net (code "76") (name "unconnected-(AT328-PD7(AIN1)-Pad11)") (class "Default")
      (node (ref "AT328") (pin "11") (pinfunction "PD7(AIN1)_11") (pintype "bidirectional"))
    )
    (net (code "77") (name "unconnected-(EXT1-PadFREE)") (class "Default")
      (node (ref "EXT1") (pin "FREE") (pinfunction "FREE_FREE") (pintype "input"))
    )
    (net (code "78") (name "unconnected-(EXT2-PadFREE)") (class "Default")
      (node (ref "EXT2") (pin "FREE") (pinfunction "FREE_FREE") (pintype "input"))
    )
    (net (code "79") (name "unconnected-(EXT3-PadFREE)") (class "Default")
      (node (ref "EXT3") (pin "FREE") (pinfunction "FREE_FREE") (pintype "input"))
    )
    (net (code "80") (name "unconnected-(EXT4-PadFREE)") (class "Default")
      (node (ref "EXT4") (pin "FREE") (pinfunction "FREE_FREE") (pintype "input"))
    )
    (net (code "81") (name "unconnected-(EXT5-PadFREE)") (class "Default")
      (node (ref "EXT5") (pin "FREE") (pinfunction "FREE_FREE") (pintype "input"))
    )
    (net (code "82") (name "unconnected-(EXT6-PadFREE)") (class "Default")
      (node (ref "EXT6") (pin "FREE") (pinfunction "FREE_FREE") (pintype "input"))
    )
    (net (code "83") (name "unconnected-(REG2A-QH*-Pad9)") (class "Default")
      (node (ref "REG2") (pin "9") (pinfunction "QH*_9") (pintype "tri_state"))
    )
    (net (code "84") (name "unconnected-(TITREUR1-Pad6)") (class "Default")
      (node (ref "TITREUR1") (pin "6") (pinfunction "6_6") (pintype "passive"))
    )
    (net (code "85") (name "unconnected-(TITREUR1-Pad9)") (class "Default")
      (node (ref "TITREUR1") (pin "9") (pinfunction "9_9") (pintype "passive"))
    )
    (net (code "86") (name "unconnected-(TITREUR1-Pad10)") (class "Default")
      (node (ref "TITREUR1") (pin "10") (pinfunction "10_10") (pintype "passive"))
    )
    (net (code "87") (name "unconnected-(TITREUR2-Pad6)") (class "Default")
      (node (ref "TITREUR2") (pin "6") (pinfunction "6_6") (pintype "passive"))
    )
    (net (code "88") (name "unconnected-(TITREUR2-Pad9)") (class "Default")
      (node (ref "TITREUR2") (pin "9") (pinfunction "9_9") (pintype "passive"))
    )
    (net (code "89") (name "unconnected-(TITREUR2-Pad10)") (class "Default")
      (node (ref "TITREUR2") (pin "10") (pinfunction "10_10") (pintype "passive"))
    )
    (net (code "90") (name "unconnected-(U$4-GPIO7-Pad26)") (class "Default")
      (node (ref "U$4") (pin "26") (pinfunction "GPIO7_26") (pintype "bidirectional"))
    )
    (net (code "91") (name "unconnected-(U$4-GPIO8-Pad24)") (class "Default")
      (node (ref "U$4") (pin "24") (pinfunction "GPIO8_24") (pintype "bidirectional"))
    )
    (net (code "92") (name "unconnected-(U$4-GPIO18-Pad12)") (class "Default")
      (node (ref "U$4") (pin "12") (pinfunction "GPIO18_12") (pintype "bidirectional"))
    )
    (net (code "93") (name "unconnected-(U$4-GPIO22-Pad15)") (class "Default")
      (node (ref "U$4") (pin "15") (pinfunction "GPIO22_15") (pintype "bidirectional"))
    )
    (net (code "94") (name "unconnected-(U$4-GPIO25-Pad22)") (class "Default")
      (node (ref "U$4") (pin "22") (pinfunction "GPIO25_22") (pintype "bidirectional"))
    )
    (net (code "95") (name "unconnected-(U$4-ID_SC-Pad28)") (class "Default")
      (node (ref "U$4") (pin "28") (pinfunction "ID_SC_28") (pintype "bidirectional"))
    )
    (net (code "96") (name "unconnected-(U$4-ID_SD-Pad27)") (class "Default")
      (node (ref "U$4") (pin "27") (pinfunction "ID_SD_27") (pintype "bidirectional"))
    )
  )
)
